# Warczok_Wojciech_168937.net
KiCad netlist of a schematic drawn in EAGLE
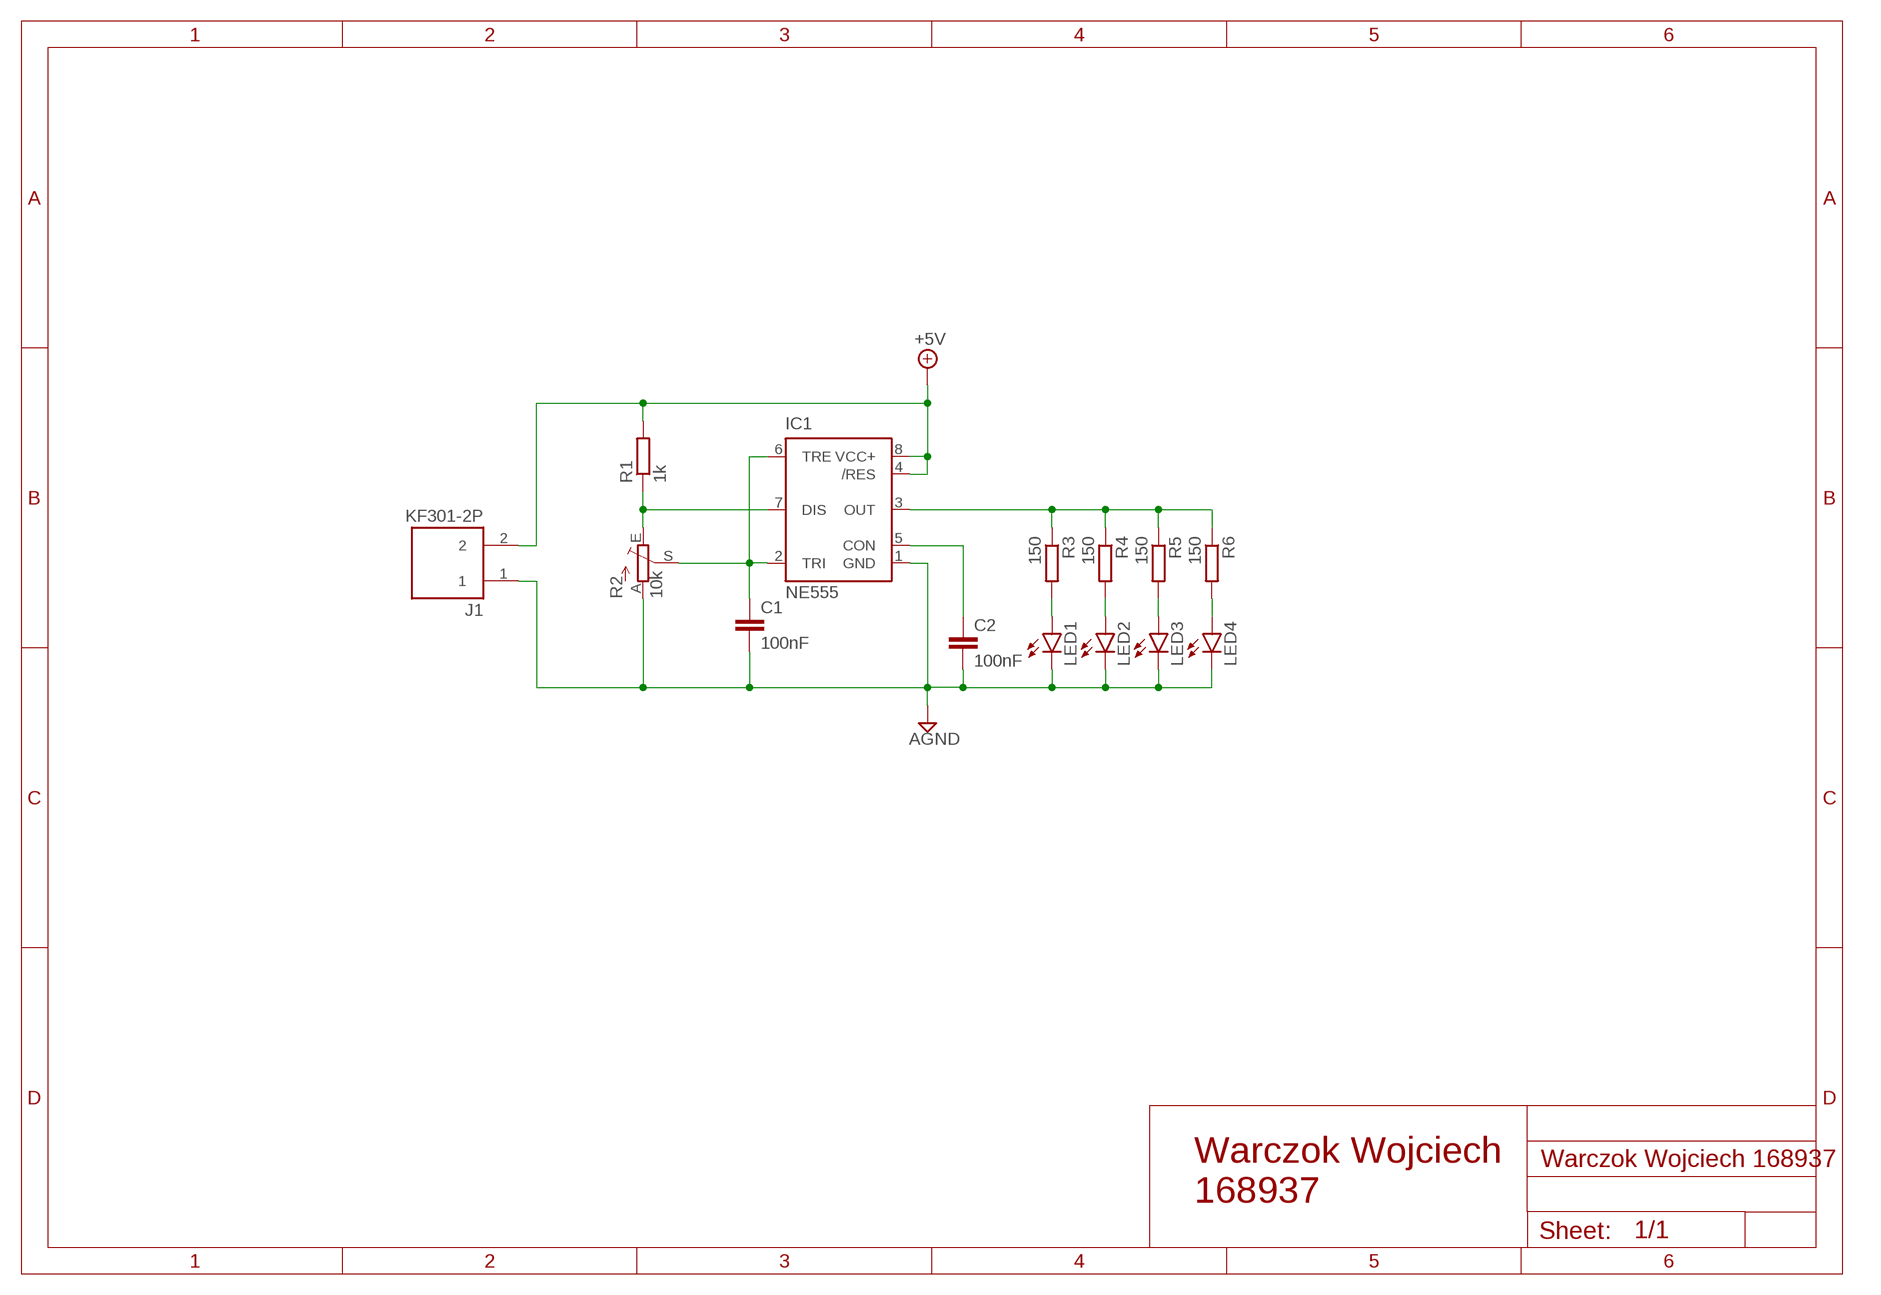
[diagram p0: schematic, sheet 1]

(export (version "E")
  (design (tool "Eeschema 10.0.6"))
  (components
    (comp (ref "C1")
      (value "100nF")
      (footprint "eagle-import:C025-024X044")
      (libsource (lib "eagle-import") (part "C-EU025-024X044"))
    )
    (comp (ref "C2")
      (value "100nF")
      (footprint "eagle-import:C025-024X044")
      (libsource (lib "eagle-import") (part "C-EU025-024X044"))
    )
    (comp (ref "IC1")
      (value "NE555")
      (footprint "eagle-import:DIL-08")
      (fields (field (name "MF") "Arrow Electronics") (field (name "MPN") "NE555N"))
      (libsource (lib "eagle-import") (part "NE555"))
    )
    (comp (ref "J1")
      (value "KF301-2P")
      (footprint "eagle-import:HANDSON_KF301-2P")
      (fields (field (name "MF") "Handson Technology"))
      (libsource (lib "eagle-import") (part "KF301-2P"))
    )
    (comp (ref "LED1")
      (value "LED5MM")
      (footprint "eagle-import:LED5MM")
      (libsource (lib "eagle-import") (part "LED5MM"))
    )
    (comp (ref "LED2")
      (value "LED5MM")
      (footprint "eagle-import:LED5MM")
      (libsource (lib "eagle-import") (part "LED5MM"))
    )
    (comp (ref "LED3")
      (value "LED5MM")
      (footprint "eagle-import:LED5MM")
      (libsource (lib "eagle-import") (part "LED5MM"))
    )
    (comp (ref "LED4")
      (value "LED5MM")
      (footprint "eagle-import:LED5MM")
      (libsource (lib "eagle-import") (part "LED5MM"))
    )
    (comp (ref "R1")
      (value "1k")
      (footprint "eagle-import:0204_7")
      (libsource (lib "eagle-import") (part "R-EU_0204/7"))
    )
    (comp (ref "R2")
      (value "10k")
      (footprint "eagle-import:CA6V")
      (libsource (lib "eagle-import") (part "TRIM_EU-CA6V"))
    )
    (comp (ref "R3")
      (value "150")
      (footprint "eagle-import:0204_7")
      (libsource (lib "eagle-import") (part "R-EU_0204/7"))
    )
    (comp (ref "R4")
      (value "150")
      (footprint "eagle-import:0204_7")
      (libsource (lib "eagle-import") (part "R-EU_0204/7"))
    )
    (comp (ref "R5")
      (value "150")
      (footprint "eagle-import:0204_7")
      (libsource (lib "eagle-import") (part "R-EU_0204/7"))
    )
    (comp (ref "R6")
      (value "150")
      (footprint "eagle-import:0204_7")
      (libsource (lib "eagle-import") (part "R-EU_0204/7"))
    )
  )
  (nets
    (net (code "1") (name "+5V") (class "Default")
      (node (ref "IC1") (pin "4") (pinfunction "/RES_4") (pintype "input"))
      (node (ref "IC1") (pin "8") (pinfunction "VCC+_8") (pintype "power_in"))
      (node (ref "J1") (pin "2") (pinfunction "2_2") (pintype "passive"))
      (node (ref "R1") (pin "2") (pinfunction "2_2") (pintype "passive"))
    )
    (net (code "2") (name "AGND") (class "Default")
      (node (ref "C1") (pin "2") (pinfunction "2_2") (pintype "passive"))
      (node (ref "C2") (pin "2") (pinfunction "2_2") (pintype "passive"))
      (node (ref "IC1") (pin "1") (pinfunction "GND_1") (pintype "power_in"))
      (node (ref "J1") (pin "1") (pinfunction "1_1") (pintype "passive"))
      (node (ref "LED1") (pin "K") (pinfunction "C_K") (pintype "passive"))
      (node (ref "LED2") (pin "K") (pinfunction "C_K") (pintype "passive"))
      (node (ref "LED3") (pin "K") (pinfunction "C_K") (pintype "passive"))
      (node (ref "LED4") (pin "K") (pinfunction "C_K") (pintype "passive"))
      (node (ref "R2") (pin "A") (pinfunction "A_A") (pintype "passive"))
    )
    (net (code "3") (name "Net-(IC1-CON)") (class "Default")
      (node (ref "C2") (pin "1") (pinfunction "1_1") (pintype "passive"))
      (node (ref "IC1") (pin "5") (pinfunction "CON_5") (pintype "input"))
    )
    (net (code "4") (name "Net-(IC1-DIS)") (class "Default")
      (node (ref "IC1") (pin "7") (pinfunction "DIS_7") (pintype "input"))
      (node (ref "R1") (pin "1") (pinfunction "1_1") (pintype "passive"))
      (node (ref "R2") (pin "E") (pinfunction "E_E") (pintype "passive"))
    )
    (net (code "5") (name "Net-(IC1-OUT)") (class "Default")
      (node (ref "IC1") (pin "3") (pinfunction "OUT_3") (pintype "output"))
      (node (ref "R3") (pin "1") (pinfunction "1_1") (pintype "passive"))
      (node (ref "R4") (pin "1") (pinfunction "1_1") (pintype "passive"))
      (node (ref "R5") (pin "1") (pinfunction "1_1") (pintype "passive"))
      (node (ref "R6") (pin "1") (pinfunction "1_1") (pintype "passive"))
    )
    (net (code "6") (name "Net-(IC1-TRE)") (class "Default")
      (node (ref "C1") (pin "1") (pinfunction "1_1") (pintype "passive"))
      (node (ref "IC1") (pin "2") (pinfunction "TRI_2") (pintype "input"))
      (node (ref "IC1") (pin "6") (pinfunction "TRE_6") (pintype "input"))
      (node (ref "R2") (pin "S") (pinfunction "S_S") (pintype "passive"))
    )
    (net (code "7") (name "Net-(LED1-PadA)") (class "Default")
      (node (ref "LED1") (pin "A") (pinfunction "A_A") (pintype "passive"))
      (node (ref "R3") (pin "2") (pinfunction "2_2") (pintype "passive"))
    )
    (net (code "8") (name "Net-(LED2-PadA)") (class "Default")
      (node (ref "LED2") (pin "A") (pinfunction "A_A") (pintype "passive"))
      (node (ref "R4") (pin "2") (pinfunction "2_2") (pintype "passive"))
    )
    (net (code "9") (name "Net-(LED3-PadA)") (class "Default")
      (node (ref "LED3") (pin "A") (pinfunction "A_A") (pintype "passive"))
      (node (ref "R5") (pin "2") (pinfunction "2_2") (pintype "passive"))
    )
    (net (code "10") (name "Net-(LED4-PadA)") (class "Default")
      (node (ref "LED4") (pin "A") (pinfunction "A_A") (pintype "passive"))
      (node (ref "R6") (pin "2") (pinfunction "2_2") (pintype "passive"))
    )
  )
)
